# WildlifeCamera.net
KiCad netlist of a schematic drawn in EAGLE
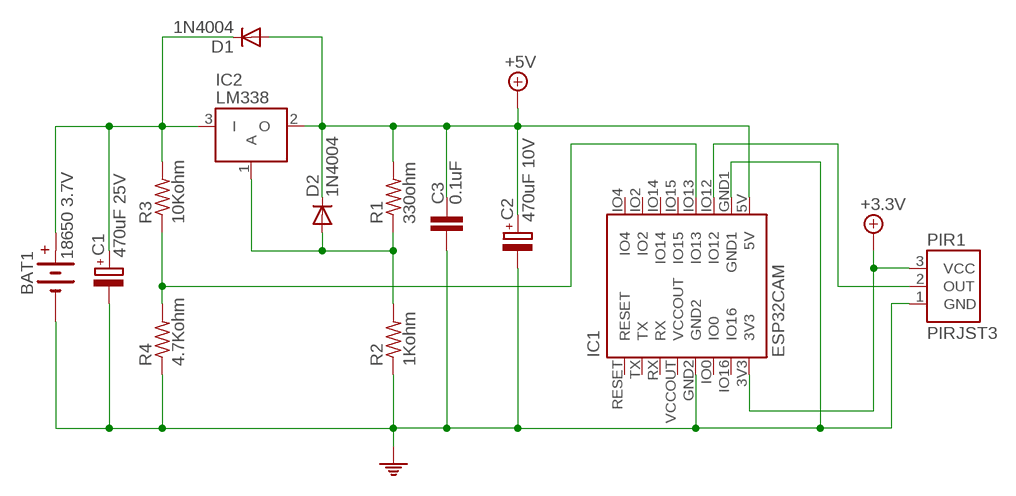
[diagram p0: schematic, sheet 1]

(export (version "E")
  (design (tool "Eeschema 10.0.6"))
  (components
    (comp (ref "BAT1")
      (value "18650 3.7V")
      (footprint "eagle-import:SIL2")
      (libsource (lib "eagle-import") (part "BATTERYSIL2"))
    )
    (comp (ref "C1")
      (value "470uF 25V")
      (footprint "eagle-import:CAPACITOR-5MM")
      (libsource (lib "eagle-import") (part "CAPACITOR_EL5MM"))
    )
    (comp (ref "C2")
      (value "470uF 10V")
      (footprint "eagle-import:CAPACITOR-5MM")
      (libsource (lib "eagle-import") (part "CAPACITOR_EL5MM"))
    )
    (comp (ref "C3")
      (value "0.1uF")
      (footprint "eagle-import:CAPACITOR-5MM")
      (libsource (lib "eagle-import") (part "CAPACITOR5MM"))
    )
    (comp (ref "D1")
      (value "1N4004")
      (footprint "eagle-import:DIODE-BIG")
      (libsource (lib "eagle-import") (part "DIODEBIG"))
    )
    (comp (ref "D2")
      (value "1N4004")
      (footprint "eagle-import:DIODE-BIG")
      (libsource (lib "eagle-import") (part "DIODEBIG"))
    )
    (comp (ref "IC1")
      (value "ESP32CAM")
      (footprint "eagle-import:ESP32CAM")
      (libsource (lib "eagle-import") (part "ESP32CAM"))
    )
    (comp (ref "IC2")
      (value "LM338")
      (footprint "eagle-import:TO220")
      (fields (field (name "SPICEPREFIX") "J"))
      (libsource (lib "eagle-import") (part "LM317TO220"))
    )
    (comp (ref "PIR1")
      (value "PIRJST3")
      (footprint "eagle-import:JST3")
      (libsource (lib "eagle-import") (part "PIRJST3"))
    )
    (comp (ref "R1")
      (value "330ohm")
      (footprint "eagle-import:RESISTOR-0.25W")
      (libsource (lib "eagle-import") (part "RESISTOR0.25W"))
    )
    (comp (ref "R2")
      (value "1Kohm")
      (footprint "eagle-import:RESISTOR-0.25W")
      (libsource (lib "eagle-import") (part "RESISTOR0.25W"))
    )
    (comp (ref "R3")
      (value "10Kohm")
      (footprint "eagle-import:RESISTOR-0.25W")
      (libsource (lib "eagle-import") (part "RESISTOR0.25W"))
    )
    (comp (ref "R4")
      (value "4.7Kohm")
      (footprint "eagle-import:RESISTOR-0.25W")
      (libsource (lib "eagle-import") (part "RESISTOR0.25W"))
    )
  )
  (nets
    (net (code "1") (name "+3.3V") (class "Default")
      (node (ref "IC1") (pin "3V3") (pinfunction "3V3_3V3") (pintype "power_in"))
      (node (ref "PIR1") (pin "3") (pinfunction "VCC_3") (pintype "power_in"))
    )
    (net (code "2") (name "+5V") (class "Default")
      (node (ref "C2") (pin "1") (pinfunction "1_1") (pintype "passive"))
      (node (ref "C3") (pin "1") (pinfunction "1_1") (pintype "passive"))
      (node (ref "D1") (pin "A") (pinfunction "A_A") (pintype "passive"))
      (node (ref "D2") (pin "C") (pinfunction "C_C") (pintype "passive"))
      (node (ref "IC1") (pin "5V") (pinfunction "5V_5V") (pintype "power_in"))
      (node (ref "IC2") (pin "2") (pinfunction "O_2") (pintype "output"))
      (node (ref "R1") (pin "2") (pinfunction "2_2") (pintype "passive"))
    )
    (net (code "3") (name "/VCCOUT") (class "Default")
      (node (ref "IC1") (pin "VCCOUT") (pinfunction "VCCOUT_VCCOUT") (pintype "power_in"))
    )
    (net (code "4") (name "GND") (class "Default")
      (node (ref "BAT1") (pin "2") (pinfunction "-_2") (pintype "passive"))
      (node (ref "C1") (pin "2") (pinfunction "2_2") (pintype "passive"))
      (node (ref "C2") (pin "2") (pinfunction "2_2") (pintype "passive"))
      (node (ref "C3") (pin "2") (pinfunction "2_2") (pintype "passive"))
      (node (ref "IC1") (pin "GND1") (pinfunction "GND1_GND1") (pintype "power_in"))
      (node (ref "IC1") (pin "GND2") (pinfunction "GND2_GND2") (pintype "power_in"))
      (node (ref "PIR1") (pin "1") (pinfunction "GND_1") (pintype "power_in"))
      (node (ref "R2") (pin "1") (pinfunction "1_1") (pintype "passive"))
      (node (ref "R4") (pin "1") (pinfunction "1_1") (pintype "passive"))
    )
    (net (code "5") (name "Net-(BAT1-+)") (class "Default")
      (node (ref "BAT1") (pin "1") (pinfunction "+_1") (pintype "passive"))
      (node (ref "C1") (pin "1") (pinfunction "1_1") (pintype "passive"))
      (node (ref "D1") (pin "C") (pinfunction "C_C") (pintype "passive"))
      (node (ref "IC2") (pin "3") (pinfunction "I_3") (pintype "input"))
      (node (ref "R3") (pin "2") (pinfunction "2_2") (pintype "passive"))
    )
    (net (code "6") (name "Net-(IC1-PadIO13)") (class "Default")
      (node (ref "IC1") (pin "IO13") (pinfunction "IO13_IO13") (pintype "bidirectional"))
      (node (ref "R3") (pin "1") (pinfunction "1_1") (pintype "passive"))
      (node (ref "R4") (pin "2") (pinfunction "2_2") (pintype "passive"))
    )
    (net (code "7") (name "Net-(IC2-A)") (class "Default")
      (node (ref "D2") (pin "A") (pinfunction "A_A") (pintype "passive"))
      (node (ref "IC2") (pin "1") (pinfunction "A_1") (pintype "input"))
      (node (ref "R1") (pin "1") (pinfunction "1_1") (pintype "passive"))
      (node (ref "R2") (pin "2") (pinfunction "2_2") (pintype "passive"))
    )
    (net (code "8") (name "Net-(PIR1-OUT)") (class "Default")
      (node (ref "IC1") (pin "IO12") (pinfunction "IO12_IO12") (pintype "bidirectional"))
      (node (ref "PIR1") (pin "2") (pinfunction "OUT_2") (pintype "output"))
    )
    (net (code "9") (name "unconnected-(IC1-PadIO0)") (class "Default")
      (node (ref "IC1") (pin "IO0") (pinfunction "IO0_IO0") (pintype "bidirectional"))
    )
    (net (code "10") (name "unconnected-(IC1-PadIO2)") (class "Default")
      (node (ref "IC1") (pin "IO2") (pinfunction "IO2_IO2") (pintype "bidirectional"))
    )
    (net (code "11") (name "unconnected-(IC1-PadIO4)") (class "Default")
      (node (ref "IC1") (pin "IO4") (pinfunction "IO4_IO4") (pintype "bidirectional"))
    )
    (net (code "12") (name "unconnected-(IC1-PadIO14)") (class "Default")
      (node (ref "IC1") (pin "IO14") (pinfunction "IO14_IO14") (pintype "bidirectional"))
    )
    (net (code "13") (name "unconnected-(IC1-PadIO15)") (class "Default")
      (node (ref "IC1") (pin "IO15") (pinfunction "IO15_IO15") (pintype "bidirectional"))
    )
    (net (code "14") (name "unconnected-(IC1-PadIO16)") (class "Default")
      (node (ref "IC1") (pin "IO16") (pinfunction "IO16_IO16") (pintype "bidirectional"))
    )
    (net (code "15") (name "unconnected-(IC1-PadRESET)") (class "Default")
      (node (ref "IC1") (pin "RESET") (pinfunction "RESET_RESET") (pintype "input"))
    )
    (net (code "16") (name "unconnected-(IC1-PadRX)") (class "Default")
      (node (ref "IC1") (pin "RX") (pinfunction "RX_RX") (pintype "bidirectional"))
    )
    (net (code "17") (name "unconnected-(IC1-PadTX)") (class "Default")
      (node (ref "IC1") (pin "TX") (pinfunction "TX_TX") (pintype "bidirectional"))
    )
  )
)
